# LAUNCHXL-F28379D_1.net
KiCad netlist of a schematic drawn in Altium Designer
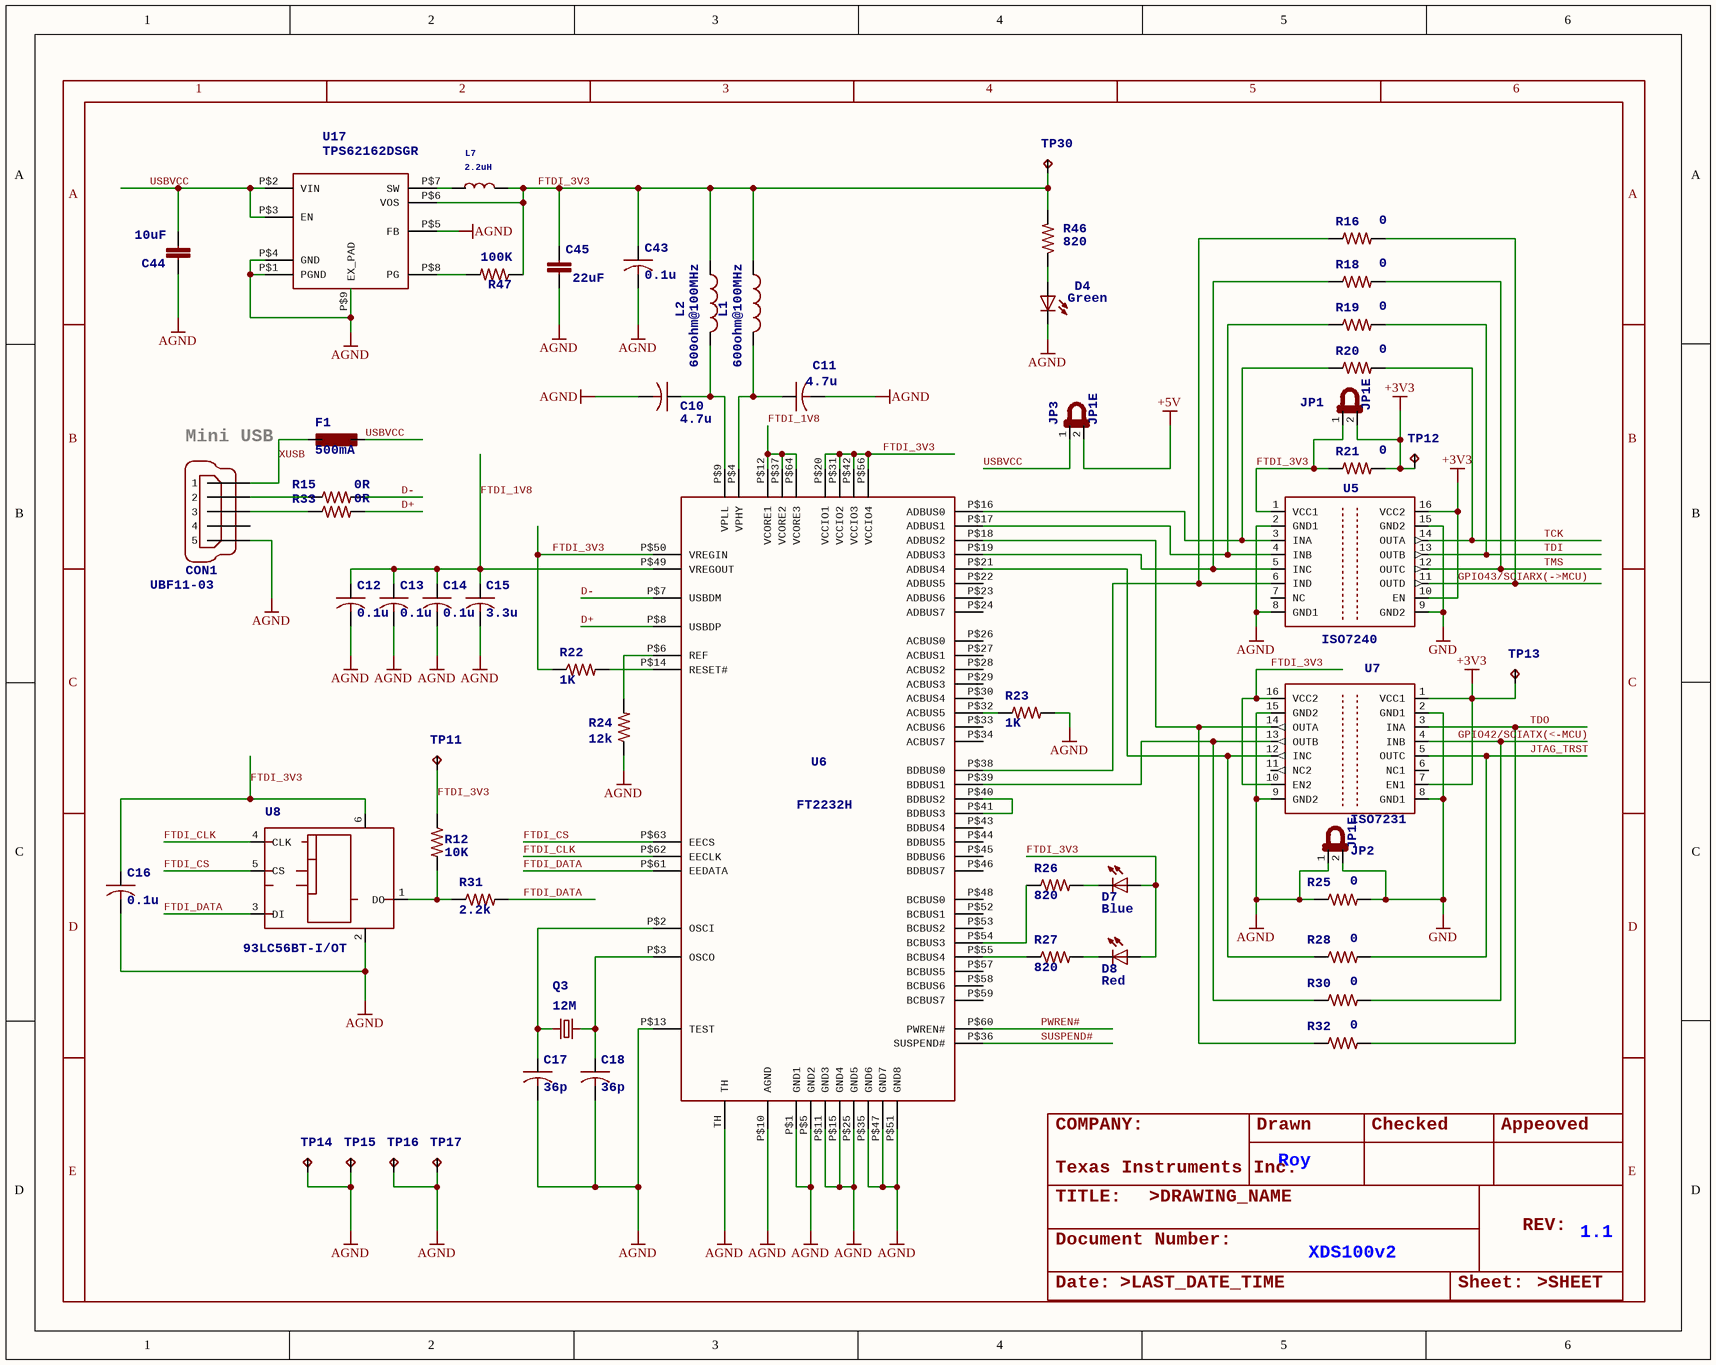
[diagram p0: LAUNCHXL-F28379D_1.SchDoc]

(export (version "E")
  (design (tool "Eeschema 10.0.6"))
  (components
    (comp (ref "C10")
      (value "4.7u")
      (footprint "C0402")
      (description "<B>CAPACITOR</B>, American symbol")
      (libsource (lib "rcl") (part "C-USC0402"))
    )
    (comp (ref "C11")
      (value "4.7u")
      (footprint "C0402")
      (description "<B>CAPACITOR</B>, American symbol")
      (libsource (lib "rcl") (part "C-USC0402"))
    )
    (comp (ref "C12")
      (value "0.1u")
      (footprint "C0402")
      (description "<B>CAPACITOR</B>, American symbol")
      (libsource (lib "rcl") (part "C-USC0402"))
    )
    (comp (ref "C13")
      (value "0.1u")
      (footprint "C0402")
      (description "<B>CAPACITOR</B>, American symbol")
      (libsource (lib "rcl") (part "C-USC0402"))
    )
    (comp (ref "C14")
      (value "0.1u")
      (footprint "C0402")
      (description "<B>CAPACITOR</B>, American symbol")
      (libsource (lib "rcl") (part "C-USC0402"))
    )
    (comp (ref "C15")
      (value "3.3u")
      (footprint "C0402")
      (description "<B>CAPACITOR</B>, American symbol")
      (libsource (lib "rcl") (part "C-USC0402"))
    )
    (comp (ref "C16")
      (value "0.1u")
      (footprint "C0402")
      (description "<B>CAPACITOR</B>, American symbol")
      (libsource (lib "rcl") (part "C-USC0402"))
    )
    (comp (ref "C17")
      (value "36p")
      (footprint "C0402")
      (description "<B>CAPACITOR</B>, American symbol")
      (libsource (lib "rcl") (part "C-USC0402"))
    )
    (comp (ref "C18")
      (value "36p")
      (footprint "C0402")
      (description "<B>CAPACITOR</B>, American symbol")
      (libsource (lib "rcl") (part "C-USC0402"))
    )
    (comp (ref "C43")
      (value "0.1u")
      (footprint "C0402")
      (description "<B>CAPACITOR</B>, American symbol")
      (libsource (lib "rcl") (part "C-USC0402"))
    )
    (comp (ref "C44")
      (value "10uF")
      (footprint "SPARKFUN_1210")
      (description "<b>Capacitor</b>\nStandard 0603 ceramic capacitor, and 0.1\" leaded capacitor.")
      (libsource (lib "RF430FRL152H_EVM_a") (part "SPARKFUN_CAP1210"))
    )
    (comp (ref "C45")
      (value "22uF")
      (footprint "SPARKFUN_1210")
      (description "<b>Capacitor</b>\nStandard 0603 ceramic capacitor, and 0.1\" leaded capacitor.")
      (libsource (lib "RF430FRL152H_EVM_a") (part "SPARKFUN_CAP1210"))
    )
    (comp (ref "CON1")
      (value "UBF11-03")
      (footprint "32005-201")
      (description "<b>MINI USB-B Conector</b><p>\nSource: www.cypressindustries.com")
      (libsource (lib "con-cypressindustries") (part "MINI-USB-32005-201"))
    )
    (comp (ref "D4")
      (value "Green")
      (footprint "CHIP-LED0603")
      (libsource (lib "led") (part "LEDCHIP-LED0603"))
    )
    (comp (ref "D7")
      (value "Blue")
      (footprint "CHIP-LED0603")
      (libsource (lib "led") (part "LEDCHIP-LED0603"))
    )
    (comp (ref "D8")
      (value "Red")
      (footprint "CHIP-LED0603")
      (libsource (lib "led") (part "LEDCHIP-LED0603"))
    )
    (comp (ref "F1")
      (value "500mA")
      (footprint "L1812")
      (description "<B>INDUCTOR</B>, European symbol")
      (libsource (lib "rcl") (part "L-EUL1812"))
    )
    (comp (ref "JP1")
      (value "JP1E")
      (footprint "JP1")
      (description "<b>JUMPER</b>")
      (libsource (lib "jumper") (part "JP1E"))
    )
    (comp (ref "JP2")
      (value "JP1E")
      (footprint "JP1")
      (description "<b>JUMPER</b>")
      (libsource (lib "jumper") (part "JP1E"))
    )
    (comp (ref "JP3")
      (value "JP1E")
      (footprint "JP1")
      (description "<b>JUMPER</b>")
      (libsource (lib "jumper") (part "JP1E"))
    )
    (comp (ref "L1")
      (value "600ohm@100MHz")
      (footprint "R0402")
      (description "<B>INDUCTOR</B>, American symbol")
      (libsource (lib "rcl") (part "L-US0402"))
    )
    (comp (ref "L2")
      (value "600ohm@100MHz")
      (footprint "R0402")
      (description "<B>INDUCTOR</B>, American symbol")
      (libsource (lib "rcl") (part "L-US0402"))
    )
    (comp (ref "L7")
      (value "2.2uH")
      (footprint "INDUCT-3.2*3.2")
      (libsource (lib "LAUNCHXL-F28027") (part "VLF4012A`"))
    )
    (comp (ref "Q3")
      (value "12M")
      (footprint "HC49UP")
      (description "<b>CRYSTAL</b>")
      (libsource (lib "crystal") (part "CRYSTALHC49UP"))
    )
    (comp (ref "R12")
      (value "10K")
      (footprint "R0402")
      (description "<B>RESISTOR</B>, American symbol")
      (libsource (lib "rcl") (part "R-US_R0402"))
    )
    (comp (ref "R15")
      (value "0R")
      (footprint "R0402")
      (description "<B>RESISTOR</B>, American symbol")
      (libsource (lib "rcl") (part "R-US_R0402"))
    )
    (comp (ref "R16")
      (value "0")
      (footprint "R1206")
      (description "<B>RESISTOR</B>, American symbol")
      (libsource (lib "rcl") (part "R-US_R1206"))
    )
    (comp (ref "R18")
      (value "0")
      (footprint "R1206")
      (description "<B>RESISTOR</B>, American symbol")
      (libsource (lib "rcl") (part "R-US_R1206"))
    )
    (comp (ref "R19")
      (value "0")
      (footprint "R1206")
      (description "<B>RESISTOR</B>, American symbol")
      (libsource (lib "rcl") (part "R-US_R1206"))
    )
    (comp (ref "R20")
      (value "0")
      (footprint "R1206")
      (description "<B>RESISTOR</B>, American symbol")
      (libsource (lib "rcl") (part "R-US_R1206"))
    )
    (comp (ref "R21")
      (value "0")
      (footprint "R1206")
      (description "<B>RESISTOR</B>, American symbol")
      (libsource (lib "rcl") (part "R-US_R1206"))
    )
    (comp (ref "R22")
      (value "1K")
      (footprint "R0402")
      (description "<B>RESISTOR</B>, American symbol")
      (libsource (lib "rcl") (part "R-US_R0402"))
    )
    (comp (ref "R23")
      (value "1K")
      (footprint "R0402")
      (description "<B>RESISTOR</B>, American symbol")
      (libsource (lib "rcl") (part "R-US_R0402"))
    )
    (comp (ref "R24")
      (value "12k")
      (footprint "R0402")
      (description "<B>RESISTOR</B>, American symbol")
      (libsource (lib "rcl") (part "R-US_R0402"))
    )
    (comp (ref "R25")
      (value "0")
      (footprint "R1206")
      (description "<B>RESISTOR</B>, American symbol")
      (libsource (lib "rcl") (part "R-US_R1206"))
    )
    (comp (ref "R26")
      (value "820")
      (footprint "R0402")
      (description "<B>RESISTOR</B>, American symbol")
      (libsource (lib "rcl") (part "R-US_R0402"))
    )
    (comp (ref "R27")
      (value "820")
      (footprint "R0402")
      (description "<B>RESISTOR</B>, American symbol")
      (libsource (lib "rcl") (part "R-US_R0402"))
    )
    (comp (ref "R28")
      (value "0")
      (footprint "R1206")
      (description "<B>RESISTOR</B>, American symbol")
      (libsource (lib "rcl") (part "R-US_R1206"))
    )
    (comp (ref "R30")
      (value "0")
      (footprint "R1206")
      (description "<B>RESISTOR</B>, American symbol")
      (libsource (lib "rcl") (part "R-US_R1206"))
    )
    (comp (ref "R31")
      (value "2.2k")
      (footprint "R0402")
      (description "<B>RESISTOR</B>, American symbol")
      (libsource (lib "rcl") (part "R-US_R0402"))
    )
    (comp (ref "R32")
      (value "0")
      (footprint "R1206")
      (description "<B>RESISTOR</B>, American symbol")
      (libsource (lib "rcl") (part "R-US_R1206"))
    )
    (comp (ref "R33")
      (value "0R")
      (footprint "R0402")
      (description "<B>RESISTOR</B>, American symbol")
      (libsource (lib "rcl") (part "R-US_R0402"))
    )
    (comp (ref "R46")
      (value "820")
      (footprint "R0402")
      (description "<B>RESISTOR</B>, American symbol")
      (libsource (lib "rcl") (part "R-US_R0402"))
    )
    (comp (ref "R47")
      (value "100K")
      (footprint "R0402")
      (description "<B>RESISTOR</B>, American symbol")
      (libsource (lib "rcl") (part "R-US_R0402"))
    )
    (comp (ref "TP11")
      (value "TESTPAD_TPB1,27")
      (footprint "TESTPAD_B1,27")
      (description "<b>Test pad</b>")
      (libsource (lib "RF430FRL152H_EVM_a") (part "TESTPAD_TPB1,27"))
    )
    (comp (ref "TP12")
      (value "TESTPAD_TPB1,27")
      (footprint "TESTPAD_B1,27")
      (description "<b>Test pad</b>")
      (libsource (lib "RF430FRL152H_EVM_a") (part "TESTPAD_TPB1,27"))
    )
    (comp (ref "TP13")
      (value "TESTPAD_TPB1,27")
      (footprint "TESTPAD_B1,27")
      (description "<b>Test pad</b>")
      (libsource (lib "RF430FRL152H_EVM_a") (part "TESTPAD_TPB1,27"))
    )
    (comp (ref "TP14")
      (value "TESTPAD_TPB1,27")
      (footprint "TESTPAD_B1,27")
      (description "<b>Test pad</b>")
      (libsource (lib "RF430FRL152H_EVM_a") (part "TESTPAD_TPB1,27"))
    )
    (comp (ref "TP15")
      (value "TESTPAD_TPB1,27")
      (footprint "TESTPAD_B1,27")
      (description "<b>Test pad</b>")
      (libsource (lib "RF430FRL152H_EVM_a") (part "TESTPAD_TPB1,27"))
    )
    (comp (ref "TP16")
      (value "TESTPAD_TPB1,27")
      (footprint "TESTPAD_B1,27")
      (description "<b>Test pad</b>")
      (libsource (lib "RF430FRL152H_EVM_a") (part "TESTPAD_TPB1,27"))
    )
    (comp (ref "TP17")
      (value "TESTPAD_TPB1,27")
      (footprint "TESTPAD_B1,27")
      (description "<b>Test pad</b>")
      (libsource (lib "RF430FRL152H_EVM_a") (part "TESTPAD_TPB1,27"))
    )
    (comp (ref "TP30")
      (value "TESTPAD_TPB1,27")
      (footprint "TESTPAD_B1,27")
      (description "<b>Test pad</b>")
      (libsource (lib "RF430FRL152H_EVM_a") (part "TESTPAD_TPB1,27"))
    )
    (comp (ref "U$2")
      (value "ROY_JUMPER")
      (footprint "ROY_JUMPER")
      (libsource (lib "roy") (part "ROY_JUMPER"))
    )
    (comp (ref "U$10")
      (value "ROY_JUMPER")
      (footprint "ROY_JUMPER")
      (libsource (lib "roy") (part "ROY_JUMPER"))
    )
    (comp (ref "U$11")
      (value "ROY_JUMPER")
      (footprint "ROY_JUMPER")
      (libsource (lib "roy") (part "ROY_JUMPER"))
    )
    (comp (ref "U5") (value "ISO7240") (footprint "SO-16DW") (libsource (lib "texas") (part "ISO7240")))
    (comp (ref "U6") (value "FT2232H") (footprint "QFN64") (libsource (lib "ti_trey") (part "FT2232H")))
    (comp (ref "U7") (value "ISO7231") (footprint "SO-16DW") (libsource (lib "texas") (part "ISO7231")))
    (comp (ref "U8")
      (value "93LC56BT-I/OT")
      (footprint "SOT23-6")
      (description "Serial <B>EPROM</B><p>\n1 K/2 K/4 K, low voltage, Microwire")
      (libsource (lib "ti_trey") (part "93*"))
    )
    (comp (ref "U17")
      (value "TPS62162DSGR")
      (footprint "TI_DSG8")
      (libsource (lib "LAUNCHXL-F28027") (part "TPS62162DSGR"))
    )
  )
  (nets
    (net (code "1") (name "+3V3") (class "Default")
      (node (ref "JP1") (pin "2") (pinfunction "2_2") (pintype "passive"))
      (node (ref "R16") (pin "2") (pinfunction "2_2") (pintype "passive"))
      (node (ref "R21") (pin "2") (pinfunction "2_2") (pintype "passive"))
      (node (ref "TP12") (pin "TP") (pinfunction "TP_TP") (pintype "passive"))
      (node (ref "TP13") (pin "TP") (pinfunction "TP_TP") (pintype "passive"))
      (node (ref "U5") (pin "10") (pinfunction "EN_10") (pintype "passive"))
      (node (ref "U5") (pin "11") (pinfunction "OUTD_11") (pintype "output"))
      (node (ref "U5") (pin "16") (pinfunction "VCC2_16") (pintype "power_in"))
      (node (ref "U7") (pin "1") (pinfunction "VCC1_1") (pintype "power_in"))
      (node (ref "U7") (pin "7") (pinfunction "EN1_7") (pintype "passive"))
    )
    (net (code "2") (name "+5V") (class "Default")
      (node (ref "JP3") (pin "2") (pinfunction "2_2") (pintype "passive"))
    )
    (net (code "3") (name "/D+") (class "Default")
      (node (ref "R33") (pin "2") (pinfunction "2_2") (pintype "passive"))
      (node (ref "U6") (pin "P$8") (pinfunction "USBDP_P$8") (pintype "passive"))
    )
    (net (code "4") (name "/D-") (class "Default")
      (node (ref "R15") (pin "2") (pinfunction "2_2") (pintype "passive"))
      (node (ref "U6") (pin "P$7") (pinfunction "USBDM_P$7") (pintype "passive"))
    )
    (net (code "5") (name "/FTDI_1V8") (class "Default")
      (node (ref "C12") (pin "1") (pinfunction "1_1") (pintype "passive"))
      (node (ref "C13") (pin "1") (pinfunction "1_1") (pintype "passive"))
      (node (ref "C14") (pin "1") (pinfunction "1_1") (pintype "passive"))
      (node (ref "C15") (pin "1") (pinfunction "1_1") (pintype "passive"))
      (node (ref "U6") (pin "P$12") (pinfunction "VCORE1_P$12") (pintype "passive"))
      (node (ref "U6") (pin "P$37") (pinfunction "VCORE2_P$37") (pintype "passive"))
      (node (ref "U6") (pin "P$49") (pinfunction "VREGOUT_P$49") (pintype "passive"))
      (node (ref "U6") (pin "P$64") (pinfunction "VCORE3_P$64") (pintype "passive"))
    )
    (net (code "6") (name "/FTDI_3V3") (class "Default")
      (node (ref "C16") (pin "1") (pinfunction "1_1") (pintype "passive"))
      (node (ref "C43") (pin "1") (pinfunction "1_1") (pintype "passive"))
      (node (ref "C45") (pin "2") (pinfunction "2_2") (pintype "passive"))
      (node (ref "D7") (pin "A") (pinfunction "A_A") (pintype "passive"))
      (node (ref "D8") (pin "A") (pinfunction "A_A") (pintype "passive"))
      (node (ref "JP1") (pin "1") (pinfunction "1_1") (pintype "passive"))
      (node (ref "L1") (pin "1") (pinfunction "1_1") (pintype "passive"))
      (node (ref "L2") (pin "1") (pinfunction "1_1") (pintype "passive"))
      (node (ref "L7") (pin "P$1") (pinfunction "1_P$1") (pintype "passive"))
      (node (ref "R12") (pin "1") (pinfunction "1_1") (pintype "passive"))
      (node (ref "R21") (pin "1") (pinfunction "1_1") (pintype "passive"))
      (node (ref "R22") (pin "1") (pinfunction "1_1") (pintype "passive"))
      (node (ref "R46") (pin "2") (pinfunction "2_2") (pintype "passive"))
      (node (ref "R47") (pin "1") (pinfunction "1_1") (pintype "passive"))
      (node (ref "TP11") (pin "TP") (pinfunction "TP_TP") (pintype "passive"))
      (node (ref "TP30") (pin "TP") (pinfunction "TP_TP") (pintype "passive"))
      (node (ref "U17") (pin "P$6") (pinfunction "VOS_P$6") (pintype "passive"))
      (node (ref "U5") (pin "1") (pinfunction "VCC1_1") (pintype "power_in"))
      (node (ref "U6") (pin "P$20") (pinfunction "VCCIO1_P$20") (pintype "passive"))
      (node (ref "U6") (pin "P$31") (pinfunction "VCCIO2_P$31") (pintype "passive"))
      (node (ref "U6") (pin "P$42") (pinfunction "VCCIO3_P$42") (pintype "passive"))
      (node (ref "U6") (pin "P$50") (pinfunction "VREGIN_P$50") (pintype "passive"))
      (node (ref "U6") (pin "P$56") (pinfunction "VCCIO4_P$56") (pintype "passive"))
      (node (ref "U7") (pin "10") (pinfunction "EN2_10") (pintype "passive"))
      (node (ref "U7") (pin "16") (pinfunction "VCC2_16") (pintype "power_in"))
      (node (ref "U8") (pin "6") (pinfunction "VCC_6") (pintype "power_in"))
    )
    (net (code "7") (name "/FTDI_CLK") (class "Default")
      (node (ref "U6") (pin "P$62") (pinfunction "EECLK_P$62") (pintype "passive"))
      (node (ref "U8") (pin "4") (pinfunction "CLK_4") (pintype "passive"))
    )
    (net (code "8") (name "/FTDI_CS") (class "Default")
      (node (ref "U6") (pin "P$63") (pinfunction "EECS_P$63") (pintype "passive"))
      (node (ref "U8") (pin "5") (pinfunction "CS_5") (pintype "passive"))
    )
    (net (code "9") (name "/FTDI_DATA") (class "Default")
      (node (ref "R31") (pin "2") (pinfunction "2_2") (pintype "passive"))
      (node (ref "U6") (pin "P$61") (pinfunction "EEDATA_P$61") (pintype "passive"))
      (node (ref "U8") (pin "3") (pinfunction "DI_3") (pintype "passive"))
    )
    (net (code "10") (name "/GPIO42{slash}SCIATX(<-MCU)") (class "Default")
      (node (ref "R30") (pin "2") (pinfunction "2_2") (pintype "passive"))
      (node (ref "U7") (pin "4") (pinfunction "INB_4") (pintype "passive"))
    )
    (net (code "11") (name "/JTAG_TRST") (class "Default")
      (node (ref "R28") (pin "2") (pinfunction "2_2") (pintype "passive"))
      (node (ref "U7") (pin "5") (pinfunction "OUTC_5") (pintype "passive"))
    )
    (net (code "12") (name "/PWREN#") (class "Default")
      (node (ref "U6") (pin "P$60") (pinfunction "PWREN#_P$60") (pintype "passive"))
    )
    (net (code "13") (name "/SUSPEND#") (class "Default")
      (node (ref "U6") (pin "P$36") (pinfunction "SUSPEND#_P$36") (pintype "passive"))
    )
    (net (code "14") (name "/TCK") (class "Default")
      (node (ref "R20") (pin "2") (pinfunction "2_2") (pintype "passive"))
      (node (ref "U5") (pin "14") (pinfunction "OUTA_14") (pintype "output"))
    )
    (net (code "15") (name "/TDI") (class "Default")
      (node (ref "R19") (pin "2") (pinfunction "2_2") (pintype "passive"))
      (node (ref "U5") (pin "13") (pinfunction "OUTB_13") (pintype "output"))
    )
    (net (code "16") (name "/TDO") (class "Default")
      (node (ref "R32") (pin "2") (pinfunction "2_2") (pintype "passive"))
      (node (ref "U7") (pin "3") (pinfunction "INA_3") (pintype "passive"))
    )
    (net (code "17") (name "/TMS") (class "Default")
      (node (ref "R18") (pin "2") (pinfunction "2_2") (pintype "passive"))
      (node (ref "U5") (pin "12") (pinfunction "OUTC_12") (pintype "output"))
    )
    (net (code "18") (name "/USBVCC") (class "Default")
      (node (ref "C44") (pin "2") (pinfunction "2_2") (pintype "passive"))
      (node (ref "F1") (pin "1") (pinfunction "1_1") (pintype "passive"))
      (node (ref "JP3") (pin "1") (pinfunction "1_1") (pintype "passive"))
      (node (ref "U17") (pin "P$2") (pinfunction "VIN_P$2") (pintype "passive"))
      (node (ref "U17") (pin "P$3") (pinfunction "EN_P$3") (pintype "passive"))
    )
    (net (code "19") (name "/XUSB") (class "Default")
      (node (ref "CON1") (pin "1") (pinfunction "1_1") (pintype "passive"))
      (node (ref "F1") (pin "2") (pinfunction "2_2") (pintype "passive"))
    )
    (net (code "20") (name "AGND") (class "Default")
      (node (ref "C10") (pin "2") (pinfunction "2_2") (pintype "passive"))
      (node (ref "C11") (pin "2") (pinfunction "2_2") (pintype "passive"))
      (node (ref "C12") (pin "2") (pinfunction "2_2") (pintype "passive"))
      (node (ref "C13") (pin "2") (pinfunction "2_2") (pintype "passive"))
      (node (ref "C14") (pin "2") (pinfunction "2_2") (pintype "passive"))
      (node (ref "C15") (pin "2") (pinfunction "2_2") (pintype "passive"))
      (node (ref "C16") (pin "2") (pinfunction "2_2") (pintype "passive"))
      (node (ref "C17") (pin "2") (pinfunction "2_2") (pintype "passive"))
      (node (ref "C18") (pin "2") (pinfunction "2_2") (pintype "passive"))
      (node (ref "C43") (pin "2") (pinfunction "2_2") (pintype "passive"))
      (node (ref "C44") (pin "1") (pinfunction "1_1") (pintype "passive"))
      (node (ref "C45") (pin "1") (pinfunction "1_1") (pintype "passive"))
      (node (ref "CON1") (pin "5") (pinfunction "5_5") (pintype "passive"))
      (node (ref "D4") (pin "C") (pinfunction "C_C") (pintype "passive"))
      (node (ref "JP2") (pin "1") (pinfunction "1_1") (pintype "passive"))
      (node (ref "R23") (pin "2") (pinfunction "2_2") (pintype "passive"))
      (node (ref "R24") (pin "1") (pinfunction "1_1") (pintype "passive"))
      (node (ref "R25") (pin "1") (pinfunction "1_1") (pintype "passive"))
      (node (ref "TP14") (pin "TP") (pinfunction "TP_TP") (pintype "passive"))
      (node (ref "TP15") (pin "TP") (pinfunction "TP_TP") (pintype "passive"))
      (node (ref "TP16") (pin "TP") (pinfunction "TP_TP") (pintype "passive"))
      (node (ref "TP17") (pin "TP") (pinfunction "TP_TP") (pintype "passive"))
      (node (ref "U17") (pin "P$1") (pinfunction "PGND_P$1") (pintype "passive"))
      (node (ref "U17") (pin "P$4") (pinfunction "GND_P$4") (pintype "passive"))
      (node (ref "U17") (pin "P$5") (pinfunction "FB_P$5") (pintype "passive"))
      (node (ref "U17") (pin "P$9") (pinfunction "EX_PAD_P$9") (pintype "passive"))
      (node (ref "U5") (pin "2") (pinfunction "GND1_2") (pintype "power_in"))
      (node (ref "U5") (pin "8") (pinfunction "GND1_8") (pintype "power_in"))
      (node (ref "U6") (pin "P$1") (pinfunction "GND1_P$1") (pintype "passive"))
      (node (ref "U6") (pin "P$10") (pinfunction "AGND_P$10") (pintype "passive"))
      (node (ref "U6") (pin "P$11") (pinfunction "GND3_P$11") (pintype "passive"))
      (node (ref "U6") (pin "P$13") (pinfunction "TEST_P$13") (pintype "passive"))
      (node (ref "U6") (pin "P$15") (pinfunction "GND4_P$15") (pintype "passive"))
      (node (ref "U6") (pin "P$25") (pinfunction "GND5_P$25") (pintype "passive"))
      (node (ref "U6") (pin "P$35") (pinfunction "GND6_P$35") (pintype "passive"))
      (node (ref "U6") (pin "P$47") (pinfunction "GND7_P$47") (pintype "passive"))
      (node (ref "U6") (pin "P$5") (pinfunction "GND2_P$5") (pintype "passive"))
      (node (ref "U6") (pin "P$51") (pinfunction "GND8_P$51") (pintype "passive"))
      (node (ref "U6") (pin "TH") (pinfunction "TH_TH") (pintype "passive"))
      (node (ref "U7") (pin "15") (pinfunction "GND2_15") (pintype "power_in"))
      (node (ref "U7") (pin "9") (pinfunction "GND2_9") (pintype "power_in"))
      (node (ref "U8") (pin "2") (pinfunction "GND_2") (pintype "power_in"))
    )
    (net (code "21") (name "GND") (class "Default")
      (node (ref "JP2") (pin "2") (pinfunction "2_2") (pintype "passive"))
      (node (ref "R25") (pin "2") (pinfunction "2_2") (pintype "passive"))
      (node (ref "U5") (pin "15") (pinfunction "GND2_15") (pintype "power_in"))
      (node (ref "U5") (pin "9") (pinfunction "GND2_9") (pintype "power_in"))
      (node (ref "U7") (pin "2") (pinfunction "GND1_2") (pintype "power_in"))
      (node (ref "U7") (pin "8") (pinfunction "GND1_8") (pintype "power_in"))
    )
    (net (code "22") (name "Net-(CON1-Pad2)") (class "Default")
      (node (ref "CON1") (pin "2") (pinfunction "2_2") (pintype "passive"))
      (node (ref "R15") (pin "1") (pinfunction "1_1") (pintype "passive"))
    )
    (net (code "23") (name "Net-(CON1-Pad3)") (class "Default")
      (node (ref "CON1") (pin "3") (pinfunction "3_3") (pintype "passive"))
      (node (ref "R33") (pin "1") (pinfunction "1_1") (pintype "passive"))
    )
    (net (code "24") (name "Net-(D4-PadA)") (class "Default")
      (node (ref "D4") (pin "A") (pinfunction "A_A") (pintype "passive"))
      (node (ref "R46") (pin "1") (pinfunction "1_1") (pintype "passive"))
    )
    (net (code "25") (name "Net-(D7-PadC)") (class "Default")
      (node (ref "D7") (pin "C") (pinfunction "C_C") (pintype "passive"))
      (node (ref "R26") (pin "2") (pinfunction "2_2") (pintype "passive"))
    )
    (net (code "26") (name "Net-(D8-PadC)") (class "Default")
      (node (ref "D8") (pin "C") (pinfunction "C_C") (pintype "passive"))
      (node (ref "R27") (pin "2") (pinfunction "2_2") (pintype "passive"))
    )
    (net (code "27") (name "Net-(L7-2)") (class "Default")
      (node (ref "L7") (pin "P$2") (pinfunction "2_P$2") (pintype "passive"))
      (node (ref "U17") (pin "P$7") (pinfunction "SW_P$7") (pintype "passive"))
    )
    (net (code "28") (name "Net-(U5-INA)") (class "Default")
      (node (ref "R20") (pin "1") (pinfunction "1_1") (pintype "passive"))
      (node (ref "U5") (pin "3") (pinfunction "INA_3") (pintype "passive"))
      (node (ref "U6") (pin "P$16") (pinfunction "ADBUS0_P$16") (pintype "passive"))
    )
    (net (code "29") (name "Net-(U5-INB)") (class "Default")
      (node (ref "R19") (pin "1") (pinfunction "1_1") (pintype "passive"))
      (node (ref "U5") (pin "4") (pinfunction "INB_4") (pintype "passive"))
      (node (ref "U6") (pin "P$17") (pinfunction "ADBUS1_P$17") (pintype "passive"))
    )
    (net (code "30") (name "Net-(U5-INC)") (class "Default")
      (node (ref "R18") (pin "1") (pinfunction "1_1") (pintype "passive"))
      (node (ref "U5") (pin "5") (pinfunction "INC_5") (pintype "passive"))
      (node (ref "U6") (pin "P$19") (pinfunction "ADBUS3_P$19") (pintype "passive"))
    )
    (net (code "31") (name "Net-(U5-IND)") (class "Default")
      (node (ref "R16") (pin "1") (pinfunction "1_1") (pintype "passive"))
      (node (ref "U5") (pin "6") (pinfunction "IND_6") (pintype "passive"))
      (node (ref "U6") (pin "P$38") (pinfunction "BDBUS0_P$38") (pintype "passive"))
    )
    (net (code "32") (name "Net-(U6-ACBUS5)") (class "Default")
      (node (ref "R23") (pin "1") (pinfunction "1_1") (pintype "passive"))
      (node (ref "U6") (pin "P$32") (pinfunction "ACBUS5_P$32") (pintype "passive"))
    )
    (net (code "33") (name "Net-(U6-ADBUS2)") (class "Default")
      (node (ref "R32") (pin "1") (pinfunction "1_1") (pintype "passive"))
      (node (ref "U6") (pin "P$18") (pinfunction "ADBUS2_P$18") (pintype "passive"))
      (node (ref "U7") (pin "14") (pinfunction "OUTA_14") (pintype "output"))
    )
    (net (code "34") (name "Net-(U6-ADBUS4)") (class "Default")
      (node (ref "R28") (pin "1") (pinfunction "1_1") (pintype "passive"))
      (node (ref "U6") (pin "P$21") (pinfunction "ADBUS4_P$21") (pintype "passive"))
      (node (ref "U7") (pin "12") (pinfunction "INC_12") (pintype "output"))
    )
    (net (code "35") (name "Net-(U6-BCBUS3)") (class "Default")
      (node (ref "R26") (pin "1") (pinfunction "1_1") (pintype "passive"))
      (node (ref "U6") (pin "P$54") (pinfunction "BCBUS3_P$54") (pintype "passive"))
    )
    (net (code "36") (name "Net-(U6-BCBUS4)") (class "Default")
      (node (ref "R27") (pin "1") (pinfunction "1_1") (pintype "passive"))
      (node (ref "U6") (pin "P$55") (pinfunction "BCBUS4_P$55") (pintype "passive"))
    )
    (net (code "37") (name "Net-(U6-BDBUS1)") (class "Default")
      (node (ref "R30") (pin "1") (pinfunction "1_1") (pintype "passive"))
      (node (ref "U6") (pin "P$39") (pinfunction "BDBUS1_P$39") (pintype "passive"))
      (node (ref "U7") (pin "13") (pinfunction "OUTB_13") (pintype "output"))
    )
    (net (code "38") (name "Net-(U6-BDBUS2)") (class "Default")
      (node (ref "U6") (pin "P$40") (pinfunction "BDBUS2_P$40") (pintype "passive"))
      (node (ref "U6") (pin "P$41") (pinfunction "BDBUS3_P$41") (pintype "passive"))
    )
    (net (code "39") (name "Net-(U6-OSCI)") (class "Default")
      (node (ref "C17") (pin "1") (pinfunction "1_1") (pintype "passive"))
      (node (ref "Q3") (pin "1") (pinfunction "1_1") (pintype "passive"))
      (node (ref "U6") (pin "P$2") (pinfunction "OSCI_P$2") (pintype "passive"))
    )
    (net (code "40") (name "Net-(U6-OSCO)") (class "Default")
      (node (ref "C18") (pin "1") (pinfunction "1_1") (pintype "passive"))
      (node (ref "Q3") (pin "2") (pinfunction "2_2") (pintype "passive"))
      (node (ref "U6") (pin "P$3") (pinfunction "OSCO_P$3") (pintype "passive"))
    )
    (net (code "41") (name "Net-(U6-REF)") (class "Default")
      (node (ref "R24") (pin "2") (pinfunction "2_2") (pintype "passive"))
      (node (ref "U6") (pin "P$6") (pinfunction "REF_P$6") (pintype "passive"))
    )
    (net (code "42") (name "Net-(U6-RESET#)") (class "Default")
      (node (ref "R22") (pin "2") (pinfunction "2_2") (pintype "passive"))
      (node (ref "U6") (pin "P$14") (pinfunction "RESET#_P$14") (pintype "passive"))
    )
    (net (code "43") (name "Net-(U6-VPHY)") (class "Default")
      (node (ref "C11") (pin "1") (pinfunction "1_1") (pintype "passive"))
      (node (ref "L1") (pin "2") (pinfunction "2_2") (pintype "passive"))
      (node (ref "U6") (pin "P$4") (pinfunction "VPHY_P$4") (pintype "passive"))
    )
    (net (code "44") (name "Net-(U6-VPLL)") (class "Default")
      (node (ref "C10") (pin "1") (pinfunction "1_1") (pintype "passive"))
      (node (ref "L2") (pin "2") (pinfunction "2_2") (pintype "passive"))
      (node (ref "U6") (pin "P$9") (pinfunction "VPLL_P$9") (pintype "passive"))
    )
    (net (code "45") (name "Net-(U8-DO)") (class "Default")
      (node (ref "R12") (pin "2") (pinfunction "2_2") (pintype "passive"))
      (node (ref "R31") (pin "1") (pinfunction "1_1") (pintype "passive"))
      (node (ref "U8") (pin "1") (pinfunction "DO_1") (pintype "tri_state"))
    )
    (net (code "46") (name "Net-(U17-PG)") (class "Default")
      (node (ref "R47") (pin "2") (pinfunction "2_2") (pintype "passive"))
      (node (ref "U17") (pin "P$8") (pinfunction "PG_P$8") (pintype "passive"))
    )
    (net (code "47") (name "unconnected-(CON1-Pad4)") (class "Default")
      (node (ref "CON1") (pin "4") (pinfunction "4_4") (pintype "passive"))
    )
    (net (code "48") (name "unconnected-(U5-NC-Pad7)") (class "Default")
      (node (ref "U5") (pin "7") (pinfunction "NC_7") (pintype "passive"))
    )
    (net (code "49") (name "unconnected-(U6-ACBUS0-PadP$26)") (class "Default")
      (node (ref "U6") (pin "P$26") (pinfunction "ACBUS0_P$26") (pintype "passive"))
    )
    (net (code "50") (name "unconnected-(U6-ACBUS1-PadP$27)") (class "Default")
      (node (ref "U6") (pin "P$27") (pinfunction "ACBUS1_P$27") (pintype "passive"))
    )
    (net (code "51") (name "unconnected-(U6-ACBUS2-PadP$28)") (class "Default")
      (node (ref "U6") (pin "P$28") (pinfunction "ACBUS2_P$28") (pintype "passive"))
    )
    (net (code "52") (name "unconnected-(U6-ACBUS3-PadP$29)") (class "Default")
      (node (ref "U6") (pin "P$29") (pinfunction "ACBUS3_P$29") (pintype "passive"))
    )
    (net (code "53") (name "unconnected-(U6-ACBUS4-PadP$30)") (class "Default")
      (node (ref "U6") (pin "P$30") (pinfunction "ACBUS4_P$30") (pintype "passive"))
    )
    (net (code "54") (name "unconnected-(U6-ACBUS6-PadP$33)") (class "Default")
      (node (ref "U6") (pin "P$33") (pinfunction "ACBUS6_P$33") (pintype "passive"))
    )
    (net (code "55") (name "unconnected-(U6-ACBUS7-PadP$34)") (class "Default")
      (node (ref "U6") (pin "P$34") (pinfunction "ACBUS7_P$34") (pintype "passive"))
    )
    (net (code "56") (name "unconnected-(U6-ADBUS5-PadP$22)") (class "Default")
      (node (ref "U6") (pin "P$22") (pinfunction "ADBUS5_P$22") (pintype "passive"))
    )
    (net (code "57") (name "unconnected-(U6-ADBUS6-PadP$23)") (class "Default")
      (node (ref "U6") (pin "P$23") (pinfunction "ADBUS6_P$23") (pintype "passive"))
    )
    (net (code "58") (name "unconnected-(U6-ADBUS7-PadP$24)") (class "Default")
      (node (ref "U6") (pin "P$24") (pinfunction "ADBUS7_P$24") (pintype "passive"))
    )
    (net (code "59") (name "unconnected-(U6-BCBUS0-PadP$48)") (class "Default")
      (node (ref "U6") (pin "P$48") (pinfunction "BCBUS0_P$48") (pintype "passive"))
    )
    (net (code "60") (name "unconnected-(U6-BCBUS1-PadP$52)") (class "Default")
      (node (ref "U6") (pin "P$52") (pinfunction "BCBUS1_P$52") (pintype "passive"))
    )
    (net (code "61") (name "unconnected-(U6-BCBUS2-PadP$53)") (class "Default")
      (node (ref "U6") (pin "P$53") (pinfunction "BCBUS2_P$53") (pintype "passive"))
    )
    (net (code "62") (name "unconnected-(U6-BCBUS5-PadP$57)") (class "Default")
      (node (ref "U6") (pin "P$57") (pinfunction "BCBUS5_P$57") (pintype "passive"))
    )
    (net (code "63") (name "unconnected-(U6-BCBUS6-PadP$58)") (class "Default")
      (node (ref "U6") (pin "P$58") (pinfunction "BCBUS6_P$58") (pintype "passive"))
    )
    (net (code "64") (name "unconnected-(U6-BCBUS7-PadP$59)") (class "Default")
      (node (ref "U6") (pin "P$59") (pinfunction "BCBUS7_P$59") (pintype "passive"))
    )
    (net (code "65") (name "unconnected-(U6-BDBUS4-PadP$43)") (class "Default")
      (node (ref "U6") (pin "P$43") (pinfunction "BDBUS4_P$43") (pintype "passive"))
    )
    (net (code "66") (name "unconnected-(U6-BDBUS5-PadP$44)") (class "Default")
      (node (ref "U6") (pin "P$44") (pinfunction "BDBUS5_P$44") (pintype "passive"))
    )
    (net (code "67") (name "unconnected-(U6-BDBUS6-PadP$45)") (class "Default")
      (node (ref "U6") (pin "P$45") (pinfunction "BDBUS6_P$45") (pintype "passive"))
    )
    (net (code "68") (name "unconnected-(U6-BDBUS7-PadP$46)") (class "Default")
      (node (ref "U6") (pin "P$46") (pinfunction "BDBUS7_P$46") (pintype "passive"))
    )
    (net (code "69") (name "unconnected-(U7-NC1-Pad6)") (class "Default")
      (node (ref "U7") (pin "6") (pinfunction "NC1_6") (pintype "passive"))
    )
    (net (code "70") (name "unconnected-(U7-NC2-Pad11)") (class "Default")
      (node (ref "U7") (pin "11") (pinfunction "NC2_11") (pintype "output"))
    )
  )
)
